# schema.net
KiCad netlist of a schematic drawn in EAGLE
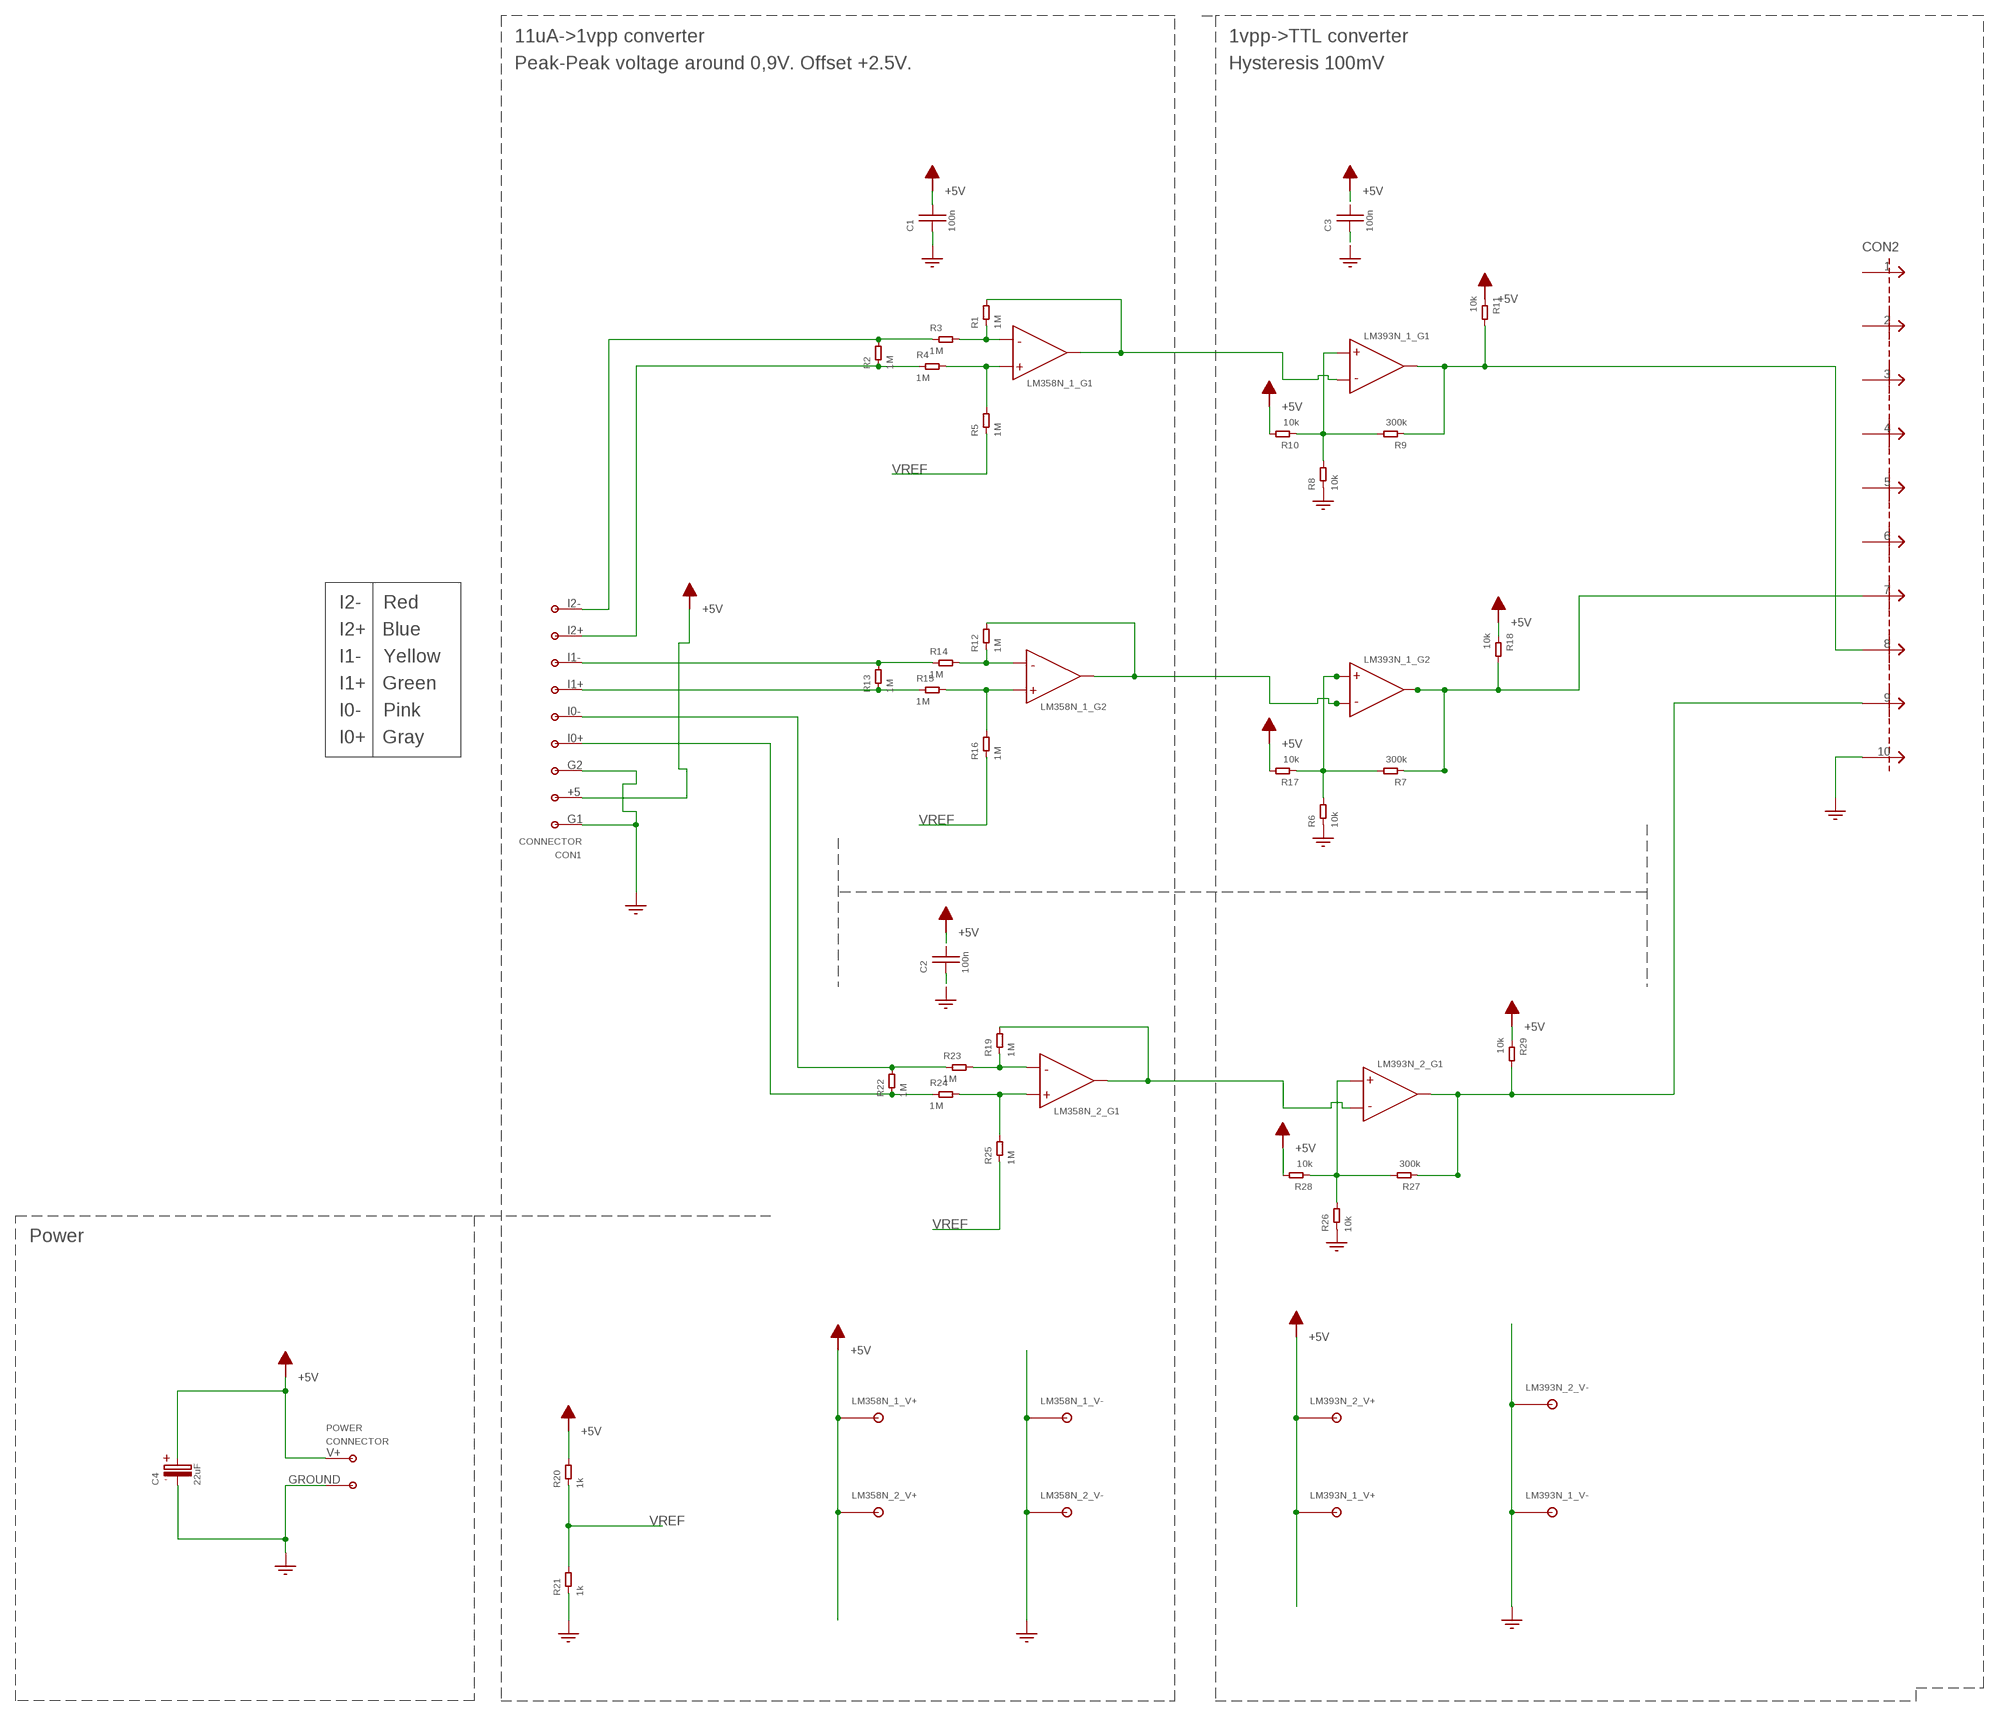
[diagram p0: schematic, sheet 1]

(export (version "E")
  (design (tool "Eeschema 10.0.6"))
  (components
    (comp (ref "C1")
      (value "100n")
      (footprint "eagle-import:R0805")
      (libsource (lib "eagle-import") (part "CC1206"))
    )
    (comp (ref "C2")
      (value "100n")
      (footprint "eagle-import:R0805")
      (libsource (lib "eagle-import") (part "CC1206"))
    )
    (comp (ref "C3")
      (value "100n")
      (footprint "eagle-import:R0805")
      (libsource (lib "eagle-import") (part "CC1206"))
    )
    (comp (ref "C4")
      (value "22uF")
      (footprint "eagle-import:E2,5-6")
      (libsource (lib "eagle-import") (part "C_POL"))
    )
    (comp (ref "CON1")
      (value "LS403_INPUT_CONNECTOR")
      (footprint "eagle-import:LS403_INPUT_CONNECTOR")
      (libsource (lib "eagle-import") (part "LS403_INPUT_CONNECTOR"))
    )
    (comp (ref "CON2")
      (value "CONNECTOR_10PINGENERIC2X5")
      (footprint "eagle-import:2X5_GENERIC")
      (fields
        (field (name "PIN10") "GND")
        (field (name "PIN7") "QA")
        (field (name "PIN8") "QB")
        (field (name "PIN9") "QIDX")
      )
      (libsource (lib "eagle-import") (part "CONNECTOR_10PINGENERIC2X5"))
    )
    (comp (ref "LM358N_1")
      (value "LM358DIL8")
      (footprint "eagle-import:DIL08")
      (libsource (lib "eagle-import") (part "LM358DIL8"))
    )
    (comp (ref "LM358N_2")
      (value "LM358DIL8")
      (footprint "eagle-import:DIL08")
      (libsource (lib "eagle-import") (part "LM358DIL8"))
    )
    (comp (ref "LM393N_1")
      (value "LM393N")
      (footprint "eagle-import:DIL08")
      (libsource (lib "eagle-import") (part "LM393N"))
    )
    (comp (ref "LM393N_2")
      (value "LM393N")
      (footprint "eagle-import:DIL08")
      (libsource (lib "eagle-import") (part "LM393N"))
    )
    (comp (ref "POWER")
      (value "2_PIN_CONNECTOR")
      (footprint "eagle-import:2_PIN_GENERIC_POWER_CONNECTOR")
      (libsource (lib "eagle-import") (part "2_PIN_CONNECTOR"))
    )
    (comp (ref "R1")
      (value "1M")
      (footprint "eagle-import:R0805")
      (libsource (lib "eagle-import") (part "RR0805"))
    )
    (comp (ref "R2")
      (value "1M")
      (footprint "eagle-import:R0805")
      (libsource (lib "eagle-import") (part "RR0805"))
    )
    (comp (ref "R3")
      (value "1M")
      (footprint "eagle-import:R0805")
      (libsource (lib "eagle-import") (part "RR0805"))
    )
    (comp (ref "R4")
      (value "1M")
      (footprint "eagle-import:R0805")
      (libsource (lib "eagle-import") (part "RR0805"))
    )
    (comp (ref "R5")
      (value "1M")
      (footprint "eagle-import:R0805")
      (libsource (lib "eagle-import") (part "RR0805"))
    )
    (comp (ref "R6")
      (value "10k")
      (footprint "eagle-import:R0805")
      (libsource (lib "eagle-import") (part "RR0805"))
    )
    (comp (ref "R7")
      (value "300k")
      (footprint "eagle-import:R0805")
      (libsource (lib "eagle-import") (part "RR0805"))
    )
    (comp (ref "R8")
      (value "10k")
      (footprint "eagle-import:R0805")
      (libsource (lib "eagle-import") (part "RR0805"))
    )
    (comp (ref "R9")
      (value "300k")
      (footprint "eagle-import:R0805")
      (libsource (lib "eagle-import") (part "RR0805"))
    )
    (comp (ref "R10")
      (value "10k")
      (footprint "eagle-import:R0805")
      (libsource (lib "eagle-import") (part "RR0805"))
    )
    (comp (ref "R11")
      (value "10k")
      (footprint "eagle-import:R0805")
      (libsource (lib "eagle-import") (part "RR0805"))
    )
    (comp (ref "R12")
      (value "1M")
      (footprint "eagle-import:R0805")
      (libsource (lib "eagle-import") (part "RR0805"))
    )
    (comp (ref "R13")
      (value "1M")
      (footprint "eagle-import:R0805")
      (libsource (lib "eagle-import") (part "RR0805"))
    )
    (comp (ref "R14")
      (value "1M")
      (footprint "eagle-import:R0805")
      (libsource (lib "eagle-import") (part "RR0805"))
    )
    (comp (ref "R15")
      (value "1M")
      (footprint "eagle-import:R0805")
      (libsource (lib "eagle-import") (part "RR0805"))
    )
    (comp (ref "R16")
      (value "1M")
      (footprint "eagle-import:R0805")
      (libsource (lib "eagle-import") (part "RR0805"))
    )
    (comp (ref "R17")
      (value "10k")
      (footprint "eagle-import:R0805")
      (libsource (lib "eagle-import") (part "RR0805"))
    )
    (comp (ref "R18")
      (value "10k")
      (footprint "eagle-import:R0805")
      (libsource (lib "eagle-import") (part "RR0805"))
    )
    (comp (ref "R19")
      (value "1M")
      (footprint "eagle-import:R0805")
      (libsource (lib "eagle-import") (part "RR0805"))
    )
    (comp (ref "R20")
      (value "1k")
      (footprint "eagle-import:R0805")
      (libsource (lib "eagle-import") (part "RR0805"))
    )
    (comp (ref "R21")
      (value "1k")
      (footprint "eagle-import:R0805")
      (libsource (lib "eagle-import") (part "RR0805"))
    )
    (comp (ref "R22")
      (value "1M")
      (footprint "eagle-import:R0805")
      (libsource (lib "eagle-import") (part "RR0805"))
    )
    (comp (ref "R23")
      (value "1M")
      (footprint "eagle-import:R0805")
      (libsource (lib "eagle-import") (part "RR0805"))
    )
    (comp (ref "R24")
      (value "1M")
      (footprint "eagle-import:R0805")
      (libsource (lib "eagle-import") (part "RR0805"))
    )
    (comp (ref "R25")
      (value "1M")
      (footprint "eagle-import:R0805")
      (libsource (lib "eagle-import") (part "RR0805"))
    )
    (comp (ref "R26")
      (value "10k")
      (footprint "eagle-import:R0805")
      (libsource (lib "eagle-import") (part "RR0805"))
    )
    (comp (ref "R27")
      (value "300k")
      (footprint "eagle-import:R0805")
      (libsource (lib "eagle-import") (part "RR0805"))
    )
    (comp (ref "R28")
      (value "10k")
      (footprint "eagle-import:R0805")
      (libsource (lib "eagle-import") (part "RR0805"))
    )
    (comp (ref "R29")
      (value "10k")
      (footprint "eagle-import:R0805")
      (libsource (lib "eagle-import") (part "RR0805"))
    )
  )
  (nets
    (net (code "1") (name "+5V") (class "Default")
      (node (ref "C1") (pin "1") (pinfunction "P$1_1") (pintype "bidirectional"))
      (node (ref "C2") (pin "1") (pinfunction "P$1_1") (pintype "bidirectional"))
      (node (ref "C3") (pin "1") (pinfunction "P$1_1") (pintype "bidirectional"))
      (node (ref "C4") (pin "+") (pinfunction "+_+") (pintype "bidirectional"))
      (node (ref "CON1") (pin "+5") (pinfunction "P$2_+5") (pintype "bidirectional"))
      (node (ref "LM358N_1") (pin "8") (pinfunction "SUPPLYPIN_8") (pintype "bidirectional"))
      (node (ref "LM358N_2") (pin "8") (pinfunction "SUPPLYPIN_8") (pintype "bidirectional"))
      (node (ref "LM393N_1") (pin "8") (pinfunction "SUPPLYPIN_8") (pintype "bidirectional"))
      (node (ref "LM393N_2") (pin "8") (pinfunction "SUPPLYPIN_8") (pintype "bidirectional"))
      (node (ref "POWER") (pin "V+") (pinfunction "P$1_V+") (pintype "bidirectional"))
      (node (ref "R10") (pin "2") (pinfunction "P$2_2") (pintype "bidirectional"))
      (node (ref "R11") (pin "1") (pinfunction "P$1_1") (pintype "bidirectional"))
      (node (ref "R17") (pin "2") (pinfunction "P$2_2") (pintype "bidirectional"))
      (node (ref "R18") (pin "1") (pinfunction "P$1_1") (pintype "bidirectional"))
      (node (ref "R20") (pin "2") (pinfunction "P$2_2") (pintype "bidirectional"))
      (node (ref "R28") (pin "2") (pinfunction "P$2_2") (pintype "bidirectional"))
      (node (ref "R29") (pin "1") (pinfunction "P$1_1") (pintype "bidirectional"))
    )
    (net (code "2") (name "/VREF") (class "Default")
      (node (ref "R16") (pin "1") (pinfunction "P$1_1") (pintype "bidirectional"))
      (node (ref "R20") (pin "1") (pinfunction "P$1_1") (pintype "bidirectional"))
      (node (ref "R21") (pin "2") (pinfunction "P$2_2") (pintype "bidirectional"))
      (node (ref "R25") (pin "1") (pinfunction "P$1_1") (pintype "bidirectional"))
      (node (ref "R5") (pin "1") (pinfunction "P$1_1") (pintype "bidirectional"))
    )
    (net (code "3") (name "GND") (class "Default")
      (node (ref "C1") (pin "2") (pinfunction "P$2_2") (pintype "bidirectional"))
      (node (ref "C2") (pin "2") (pinfunction "P$2_2") (pintype "bidirectional"))
      (node (ref "C3") (pin "2") (pinfunction "P$2_2") (pintype "bidirectional"))
      (node (ref "C4") (pin "-") (pinfunction "-_-") (pintype "bidirectional"))
      (node (ref "CON1") (pin "G1") (pinfunction "P$1_G1") (pintype "bidirectional"))
      (node (ref "CON1") (pin "G2") (pinfunction "P$3_G2") (pintype "bidirectional"))
      (node (ref "CON2") (pin "10") (pinfunction "P$10_10") (pintype "bidirectional"))
      (node (ref "LM358N_1") (pin "4") (pinfunction "SUPPLYPIN_4") (pintype "bidirectional"))
      (node (ref "LM358N_2") (pin "4") (pinfunction "SUPPLYPIN_4") (pintype "bidirectional"))
      (node (ref "LM393N_1") (pin "4") (pinfunction "SUPPLYPIN_4") (pintype "bidirectional"))
      (node (ref "LM393N_2") (pin "4") (pinfunction "SUPPLYPIN_4") (pintype "bidirectional"))
      (node (ref "POWER") (pin "GROUND") (pinfunction "P$2_GROUND") (pintype "bidirectional"))
      (node (ref "R21") (pin "1") (pinfunction "P$1_1") (pintype "bidirectional"))
      (node (ref "R26") (pin "1") (pinfunction "P$1_1") (pintype "bidirectional"))
      (node (ref "R6") (pin "1") (pinfunction "P$1_1") (pintype "bidirectional"))
      (node (ref "R8") (pin "1") (pinfunction "P$1_1") (pintype "bidirectional"))
    )
    (net (code "4") (name "Net-(CON1-P$4)") (class "Default")
      (node (ref "CON1") (pin "I0+") (pinfunction "P$4_I0+") (pintype "bidirectional"))
      (node (ref "R22") (pin "1") (pinfunction "P$1_1") (pintype "bidirectional"))
      (node (ref "R24") (pin "1") (pinfunction "P$1_1") (pintype "bidirectional"))
    )
    (net (code "5") (name "Net-(CON1-P$5)") (class "Default")
      (node (ref "CON1") (pin "I0-") (pinfunction "P$5_I0-") (pintype "bidirectional"))
      (node (ref "R22") (pin "2") (pinfunction "P$2_2") (pintype "bidirectional"))
      (node (ref "R23") (pin "1") (pinfunction "P$1_1") (pintype "bidirectional"))
    )
    (net (code "6") (name "Net-(CON1-P$6)") (class "Default")
      (node (ref "CON1") (pin "I1+") (pinfunction "P$6_I1+") (pintype "bidirectional"))
      (node (ref "R13") (pin "1") (pinfunction "P$1_1") (pintype "bidirectional"))
      (node (ref "R15") (pin "1") (pinfunction "P$1_1") (pintype "bidirectional"))
    )
    (net (code "7") (name "Net-(CON1-P$7)") (class "Default")
      (node (ref "CON1") (pin "I1-") (pinfunction "P$7_I1-") (pintype "bidirectional"))
      (node (ref "R13") (pin "2") (pinfunction "P$2_2") (pintype "bidirectional"))
      (node (ref "R14") (pin "1") (pinfunction "P$1_1") (pintype "bidirectional"))
    )
    (net (code "8") (name "Net-(CON1-P$8)") (class "Default")
      (node (ref "CON1") (pin "I2+") (pinfunction "P$8_I2+") (pintype "bidirectional"))
      (node (ref "R2") (pin "1") (pinfunction "P$1_1") (pintype "bidirectional"))
      (node (ref "R4") (pin "1") (pinfunction "P$1_1") (pintype "bidirectional"))
    )
    (net (code "9") (name "Net-(CON1-P$9)") (class "Default")
      (node (ref "CON1") (pin "I2-") (pinfunction "P$9_I2-") (pintype "bidirectional"))
      (node (ref "R2") (pin "2") (pinfunction "P$2_2") (pintype "bidirectional"))
      (node (ref "R3") (pin "1") (pinfunction "P$1_1") (pintype "bidirectional"))
    )
    (net (code "10") (name "Net-(CON2-P$7)") (class "Default")
      (node (ref "CON2") (pin "7") (pinfunction "P$7_7") (pintype "bidirectional"))
      (node (ref "LM393N_1") (pin "7") (pinfunction "OUT_7") (pintype "bidirectional"))
      (node (ref "R18") (pin "2") (pinfunction "P$2_2") (pintype "bidirectional"))
      (node (ref "R7") (pin "1") (pinfunction "P$1_1") (pintype "bidirectional"))
    )
    (net (code "11") (name "Net-(CON2-P$8)") (class "Default")
      (node (ref "CON2") (pin "8") (pinfunction "P$8_8") (pintype "bidirectional"))
      (node (ref "LM393N_1") (pin "1") (pinfunction "OUT_1") (pintype "bidirectional"))
      (node (ref "R11") (pin "2") (pinfunction "P$2_2") (pintype "bidirectional"))
      (node (ref "R9") (pin "1") (pinfunction "P$1_1") (pintype "bidirectional"))
    )
    (net (code "12") (name "Net-(CON2-P$9)") (class "Default")
      (node (ref "CON2") (pin "9") (pinfunction "P$9_9") (pintype "bidirectional"))
      (node (ref "LM393N_2") (pin "1") (pinfunction "OUT_1") (pintype "bidirectional"))
      (node (ref "R27") (pin "1") (pinfunction "P$1_1") (pintype "bidirectional"))
      (node (ref "R29") (pin "2") (pinfunction "P$2_2") (pintype "bidirectional"))
    )
    (net (code "13") (name "Net-(LM358N_1A-+)") (class "Default")
      (node (ref "LM358N_1") (pin "3") (pinfunction "+_3") (pintype "bidirectional"))
      (node (ref "R4") (pin "2") (pinfunction "P$2_2") (pintype "bidirectional"))
      (node (ref "R5") (pin "2") (pinfunction "P$2_2") (pintype "bidirectional"))
    )
    (net (code "14") (name "Net-(LM358N_1A--)") (class "Default")
      (node (ref "LM358N_1") (pin "2") (pinfunction "-_2") (pintype "bidirectional"))
      (node (ref "R1") (pin "1") (pinfunction "P$1_1") (pintype "bidirectional"))
      (node (ref "R3") (pin "2") (pinfunction "P$2_2") (pintype "bidirectional"))
    )
    (net (code "15") (name "Net-(LM358N_1A-OUT)") (class "Default")
      (node (ref "LM358N_1") (pin "1") (pinfunction "OUT_1") (pintype "bidirectional"))
      (node (ref "LM393N_1") (pin "2") (pinfunction "-_2") (pintype "bidirectional"))
      (node (ref "R1") (pin "2") (pinfunction "P$2_2") (pintype "bidirectional"))
    )
    (net (code "16") (name "Net-(LM358N_1B-+)") (class "Default")
      (node (ref "LM358N_1") (pin "5") (pinfunction "+_5") (pintype "bidirectional"))
      (node (ref "R15") (pin "2") (pinfunction "P$2_2") (pintype "bidirectional"))
      (node (ref "R16") (pin "2") (pinfunction "P$2_2") (pintype "bidirectional"))
    )
    (net (code "17") (name "Net-(LM358N_1B--)") (class "Default")
      (node (ref "LM358N_1") (pin "6") (pinfunction "-_6") (pintype "bidirectional"))
      (node (ref "R12") (pin "1") (pinfunction "P$1_1") (pintype "bidirectional"))
      (node (ref "R14") (pin "2") (pinfunction "P$2_2") (pintype "bidirectional"))
    )
    (net (code "18") (name "Net-(LM358N_1B-OUT)") (class "Default")
      (node (ref "LM358N_1") (pin "7") (pinfunction "OUT_7") (pintype "bidirectional"))
      (node (ref "LM393N_1") (pin "6") (pinfunction "-_6") (pintype "bidirectional"))
      (node (ref "R12") (pin "2") (pinfunction "P$2_2") (pintype "bidirectional"))
    )
    (net (code "19") (name "Net-(LM358N_2A-+)") (class "Default")
      (node (ref "LM358N_2") (pin "3") (pinfunction "+_3") (pintype "bidirectional"))
      (node (ref "R24") (pin "2") (pinfunction "P$2_2") (pintype "bidirectional"))
      (node (ref "R25") (pin "2") (pinfunction "P$2_2") (pintype "bidirectional"))
    )
    (net (code "20") (name "Net-(LM358N_2A--)") (class "Default")
      (node (ref "LM358N_2") (pin "2") (pinfunction "-_2") (pintype "bidirectional"))
      (node (ref "R19") (pin "1") (pinfunction "P$1_1") (pintype "bidirectional"))
      (node (ref "R23") (pin "2") (pinfunction "P$2_2") (pintype "bidirectional"))
    )
    (net (code "21") (name "Net-(LM358N_2A-OUT)") (class "Default")
      (node (ref "LM358N_2") (pin "1") (pinfunction "OUT_1") (pintype "bidirectional"))
      (node (ref "LM393N_2") (pin "2") (pinfunction "-_2") (pintype "bidirectional"))
      (node (ref "R19") (pin "2") (pinfunction "P$2_2") (pintype "bidirectional"))
    )
    (net (code "22") (name "Net-(LM393N_1A-+)") (class "Default")
      (node (ref "LM393N_1") (pin "3") (pinfunction "+_3") (pintype "bidirectional"))
      (node (ref "R10") (pin "1") (pinfunction "P$1_1") (pintype "bidirectional"))
      (node (ref "R8") (pin "2") (pinfunction "P$2_2") (pintype "bidirectional"))
      (node (ref "R9") (pin "2") (pinfunction "P$2_2") (pintype "bidirectional"))
    )
    (net (code "23") (name "Net-(LM393N_1B-+)") (class "Default")
      (node (ref "LM393N_1") (pin "5") (pinfunction "+_5") (pintype "bidirectional"))
      (node (ref "R17") (pin "1") (pinfunction "P$1_1") (pintype "bidirectional"))
      (node (ref "R6") (pin "2") (pinfunction "P$2_2") (pintype "bidirectional"))
      (node (ref "R7") (pin "2") (pinfunction "P$2_2") (pintype "bidirectional"))
    )
    (net (code "24") (name "Net-(LM393N_2A-+)") (class "Default")
      (node (ref "LM393N_2") (pin "3") (pinfunction "+_3") (pintype "bidirectional"))
      (node (ref "R26") (pin "2") (pinfunction "P$2_2") (pintype "bidirectional"))
      (node (ref "R27") (pin "2") (pinfunction "P$2_2") (pintype "bidirectional"))
      (node (ref "R28") (pin "1") (pinfunction "P$1_1") (pintype "bidirectional"))
    )
    (net (code "25") (name "unconnected-(CON2-P$1-Pad1)") (class "Default")
      (node (ref "CON2") (pin "1") (pinfunction "P$1_1") (pintype "bidirectional"))
    )
    (net (code "26") (name "unconnected-(CON2-P$2-Pad2)") (class "Default")
      (node (ref "CON2") (pin "2") (pinfunction "P$2_2") (pintype "bidirectional"))
    )
    (net (code "27") (name "unconnected-(CON2-P$3-Pad3)") (class "Default")
      (node (ref "CON2") (pin "3") (pinfunction "P$3_3") (pintype "bidirectional"))
    )
    (net (code "28") (name "unconnected-(CON2-P$4-Pad4)") (class "Default")
      (node (ref "CON2") (pin "4") (pinfunction "P$4_4") (pintype "bidirectional"))
    )
    (net (code "29") (name "unconnected-(CON2-P$5-Pad5)") (class "Default")
      (node (ref "CON2") (pin "5") (pinfunction "P$5_5") (pintype "bidirectional"))
    )
    (net (code "30") (name "unconnected-(CON2-P$6-Pad6)") (class "Default")
      (node (ref "CON2") (pin "6") (pinfunction "P$6_6") (pintype "bidirectional"))
    )
  )
)
